# untitled.net
KiCad netlist of a schematic drawn in EAGLE
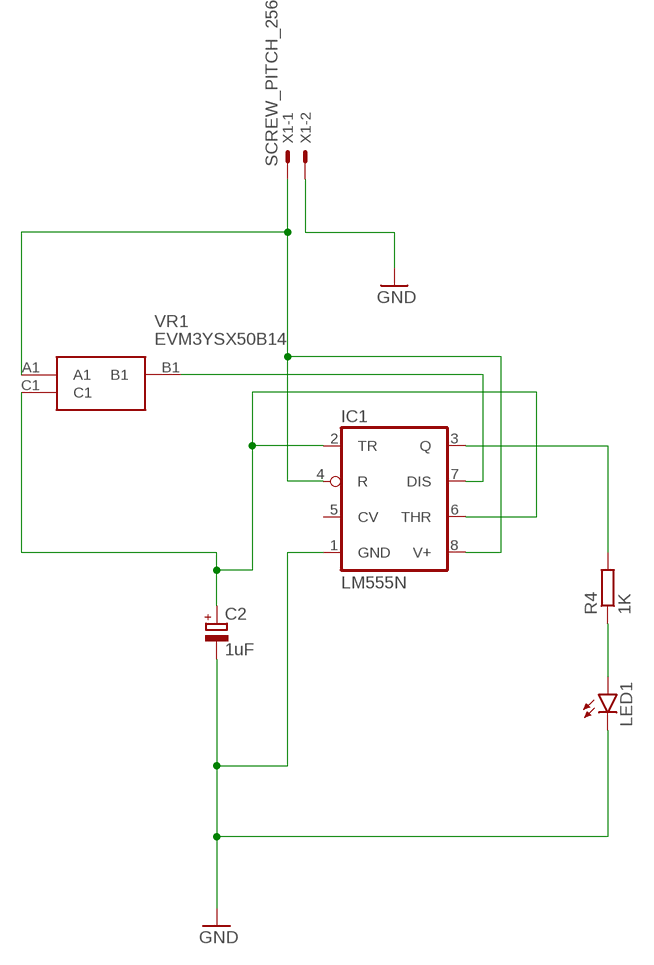
[diagram p0: schematic, sheet 1]

(export (version "E")
  (design (tool "Eeschema 10.0.6"))
  (components
    (comp (ref "C2")
      (value "1uF")
      (footprint "eagle-import:E2-5")
      (libsource (lib "eagle-import") (part "CPOL-EUE2-5"))
    )
    (comp (ref "IC1")
      (value "LM555N")
      (footprint "eagle-import:DIL08")
      (libsource (lib "eagle-import") (part "555NLM"))
    )
    (comp (ref "LED1")
      (value "LED_1206SMT1206")
      (footprint "eagle-import:1206")
      (libsource (lib "eagle-import") (part "LED_1206SMT1206"))
    )
    (comp (ref "R4")
      (value "1K")
      (footprint "eagle-import:0207_10")
      (libsource (lib "eagle-import") (part "CARBON/METAL_FILM_RESISTOR0207/10"))
    )
    (comp (ref "VR1")
      (value "EVM3YSX50B14")
      (footprint "eagle-import:EVM3YSX50B14")
      (libsource (lib "eagle-import") (part "EVM3YSX50B14"))
    )
    (comp (ref "X1")
      (value "SCREW_PITCH_256")
      (footprint "eagle-import:22-23-2021")
      (fields (field (name "MF") "MOLEX") (field (name "MPN") "22-23-2021"))
      (libsource (lib "eagle-import") (part "SCREW_PITCH_256"))
    )
  )
  (nets
    (net (code "1") (name "GND") (class "Default")
      (node (ref "C2") (pin "-") (pinfunction "-_-") (pintype "passive"))
      (node (ref "IC1") (pin "1") (pinfunction "GND_1") (pintype "power_in"))
      (node (ref "LED1") (pin "C") (pinfunction "C_C") (pintype "passive"))
      (node (ref "X1") (pin "2") (pinfunction "S_2") (pintype "passive"))
    )
    (net (code "2") (name "Net-(IC1-DIS)") (class "Default")
      (node (ref "IC1") (pin "7") (pinfunction "DIS_7") (pintype "input"))
      (node (ref "VR1") (pin "B1") (pinfunction "B1_B1") (pintype "bidirectional"))
    )
    (net (code "3") (name "Net-(IC1-Q)") (class "Default")
      (node (ref "IC1") (pin "3") (pinfunction "Q_3") (pintype "output"))
      (node (ref "R4") (pin "2") (pinfunction "2_2") (pintype "passive"))
    )
    (net (code "4") (name "Net-(IC1-R)") (class "Default")
      (node (ref "IC1") (pin "4") (pinfunction "R_4") (pintype "input"))
      (node (ref "IC1") (pin "8") (pinfunction "V+_8") (pintype "power_in"))
      (node (ref "VR1") (pin "A1") (pinfunction "A1_A1") (pintype "bidirectional"))
      (node (ref "X1") (pin "1") (pinfunction "S_1") (pintype "passive"))
    )
    (net (code "5") (name "Net-(IC1-THR)") (class "Default")
      (node (ref "C2") (pin "+") (pinfunction "+_+") (pintype "passive"))
      (node (ref "IC1") (pin "2") (pinfunction "TR_2") (pintype "input"))
      (node (ref "IC1") (pin "6") (pinfunction "THR_6") (pintype "input"))
      (node (ref "VR1") (pin "C1") (pinfunction "C1_C1") (pintype "bidirectional"))
    )
    (net (code "6") (name "Net-(LED1-PadA)") (class "Default")
      (node (ref "LED1") (pin "A") (pinfunction "A_A") (pintype "passive"))
      (node (ref "R4") (pin "1") (pinfunction "1_1") (pintype "passive"))
    )
    (net (code "7") (name "unconnected-(IC1-CV-Pad5)") (class "Default")
      (node (ref "IC1") (pin "5") (pinfunction "CV_5") (pintype "input"))
    )
  )
)
